# writer.net
KiCad netlist of a schematic drawn in EAGLE
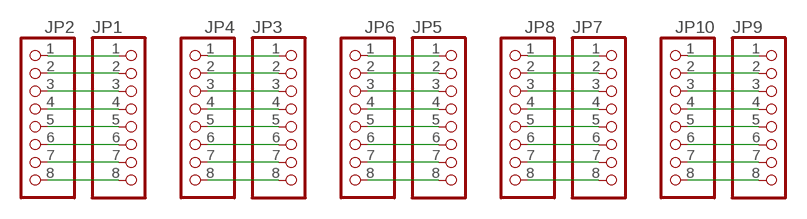
[diagram p0: schematic, sheet 1]

(export (version "E")
  (design (tool "Eeschema 10.0.6"))
  (components
    (comp (ref "JP1")
      (value "PINHD-1X8")
      (footprint "eagle-import:1X08")
      (libsource (lib "eagle-import") (part "PINHD-1X8"))
    )
    (comp (ref "JP2")
      (value "PINHD-1X8")
      (footprint "eagle-import:1X08")
      (libsource (lib "eagle-import") (part "PINHD-1X8"))
    )
    (comp (ref "JP3")
      (value "PINHD-1X8")
      (footprint "eagle-import:1X08")
      (libsource (lib "eagle-import") (part "PINHD-1X8"))
    )
    (comp (ref "JP4")
      (value "PINHD-1X8")
      (footprint "eagle-import:1X08")
      (libsource (lib "eagle-import") (part "PINHD-1X8"))
    )
    (comp (ref "JP5")
      (value "PINHD-1X8")
      (footprint "eagle-import:1X08")
      (libsource (lib "eagle-import") (part "PINHD-1X8"))
    )
    (comp (ref "JP6")
      (value "PINHD-1X8")
      (footprint "eagle-import:1X08")
      (libsource (lib "eagle-import") (part "PINHD-1X8"))
    )
    (comp (ref "JP7")
      (value "PINHD-1X8")
      (footprint "eagle-import:1X08")
      (libsource (lib "eagle-import") (part "PINHD-1X8"))
    )
    (comp (ref "JP8")
      (value "PINHD-1X8")
      (footprint "eagle-import:1X08")
      (libsource (lib "eagle-import") (part "PINHD-1X8"))
    )
    (comp (ref "JP9")
      (value "PINHD-1X8")
      (footprint "eagle-import:1X08")
      (libsource (lib "eagle-import") (part "PINHD-1X8"))
    )
    (comp (ref "JP10")
      (value "PINHD-1X8")
      (footprint "eagle-import:1X08")
      (libsource (lib "eagle-import") (part "PINHD-1X8"))
    )
  )
  (nets
    (net (code "1") (name "Net-(JP1-Pad1)") (class "Default")
      (node (ref "JP1") (pin "1") (pinfunction "1_1") (pintype "passive"))
      (node (ref "JP2") (pin "1") (pinfunction "1_1") (pintype "passive"))
    )
    (net (code "2") (name "Net-(JP1-Pad2)") (class "Default")
      (node (ref "JP1") (pin "2") (pinfunction "2_2") (pintype "passive"))
      (node (ref "JP2") (pin "2") (pinfunction "2_2") (pintype "passive"))
    )
    (net (code "3") (name "Net-(JP1-Pad3)") (class "Default")
      (node (ref "JP1") (pin "3") (pinfunction "3_3") (pintype "passive"))
      (node (ref "JP2") (pin "3") (pinfunction "3_3") (pintype "passive"))
    )
    (net (code "4") (name "Net-(JP1-Pad4)") (class "Default")
      (node (ref "JP1") (pin "4") (pinfunction "4_4") (pintype "passive"))
      (node (ref "JP2") (pin "4") (pinfunction "4_4") (pintype "passive"))
    )
    (net (code "5") (name "Net-(JP1-Pad5)") (class "Default")
      (node (ref "JP1") (pin "5") (pinfunction "5_5") (pintype "passive"))
      (node (ref "JP2") (pin "5") (pinfunction "5_5") (pintype "passive"))
    )
    (net (code "6") (name "Net-(JP1-Pad6)") (class "Default")
      (node (ref "JP1") (pin "6") (pinfunction "6_6") (pintype "passive"))
      (node (ref "JP2") (pin "6") (pinfunction "6_6") (pintype "passive"))
    )
    (net (code "7") (name "Net-(JP1-Pad7)") (class "Default")
      (node (ref "JP1") (pin "7") (pinfunction "7_7") (pintype "passive"))
      (node (ref "JP2") (pin "7") (pinfunction "7_7") (pintype "passive"))
    )
    (net (code "8") (name "Net-(JP1-Pad8)") (class "Default")
      (node (ref "JP1") (pin "8") (pinfunction "8_8") (pintype "passive"))
      (node (ref "JP2") (pin "8") (pinfunction "8_8") (pintype "passive"))
    )
    (net (code "9") (name "Net-(JP3-Pad1)") (class "Default")
      (node (ref "JP3") (pin "1") (pinfunction "1_1") (pintype "passive"))
      (node (ref "JP4") (pin "1") (pinfunction "1_1") (pintype "passive"))
    )
    (net (code "10") (name "Net-(JP3-Pad2)") (class "Default")
      (node (ref "JP3") (pin "2") (pinfunction "2_2") (pintype "passive"))
      (node (ref "JP4") (pin "2") (pinfunction "2_2") (pintype "passive"))
    )
    (net (code "11") (name "Net-(JP3-Pad3)") (class "Default")
      (node (ref "JP3") (pin "3") (pinfunction "3_3") (pintype "passive"))
      (node (ref "JP4") (pin "3") (pinfunction "3_3") (pintype "passive"))
    )
    (net (code "12") (name "Net-(JP3-Pad4)") (class "Default")
      (node (ref "JP3") (pin "4") (pinfunction "4_4") (pintype "passive"))
      (node (ref "JP4") (pin "4") (pinfunction "4_4") (pintype "passive"))
    )
    (net (code "13") (name "Net-(JP3-Pad5)") (class "Default")
      (node (ref "JP3") (pin "5") (pinfunction "5_5") (pintype "passive"))
      (node (ref "JP4") (pin "5") (pinfunction "5_5") (pintype "passive"))
    )
    (net (code "14") (name "Net-(JP3-Pad6)") (class "Default")
      (node (ref "JP3") (pin "6") (pinfunction "6_6") (pintype "passive"))
      (node (ref "JP4") (pin "6") (pinfunction "6_6") (pintype "passive"))
    )
    (net (code "15") (name "Net-(JP3-Pad7)") (class "Default")
      (node (ref "JP3") (pin "7") (pinfunction "7_7") (pintype "passive"))
      (node (ref "JP4") (pin "7") (pinfunction "7_7") (pintype "passive"))
    )
    (net (code "16") (name "Net-(JP3-Pad8)") (class "Default")
      (node (ref "JP3") (pin "8") (pinfunction "8_8") (pintype "passive"))
      (node (ref "JP4") (pin "8") (pinfunction "8_8") (pintype "passive"))
    )
    (net (code "17") (name "Net-(JP5-Pad1)") (class "Default")
      (node (ref "JP5") (pin "1") (pinfunction "1_1") (pintype "passive"))
      (node (ref "JP6") (pin "1") (pinfunction "1_1") (pintype "passive"))
    )
    (net (code "18") (name "Net-(JP5-Pad2)") (class "Default")
      (node (ref "JP5") (pin "2") (pinfunction "2_2") (pintype "passive"))
      (node (ref "JP6") (pin "2") (pinfunction "2_2") (pintype "passive"))
    )
    (net (code "19") (name "Net-(JP5-Pad3)") (class "Default")
      (node (ref "JP5") (pin "3") (pinfunction "3_3") (pintype "passive"))
      (node (ref "JP6") (pin "3") (pinfunction "3_3") (pintype "passive"))
    )
    (net (code "20") (name "Net-(JP5-Pad4)") (class "Default")
      (node (ref "JP5") (pin "4") (pinfunction "4_4") (pintype "passive"))
      (node (ref "JP6") (pin "4") (pinfunction "4_4") (pintype "passive"))
    )
    (net (code "21") (name "Net-(JP5-Pad5)") (class "Default")
      (node (ref "JP5") (pin "5") (pinfunction "5_5") (pintype "passive"))
      (node (ref "JP6") (pin "5") (pinfunction "5_5") (pintype "passive"))
    )
    (net (code "22") (name "Net-(JP5-Pad6)") (class "Default")
      (node (ref "JP5") (pin "6") (pinfunction "6_6") (pintype "passive"))
      (node (ref "JP6") (pin "6") (pinfunction "6_6") (pintype "passive"))
    )
    (net (code "23") (name "Net-(JP5-Pad7)") (class "Default")
      (node (ref "JP5") (pin "7") (pinfunction "7_7") (pintype "passive"))
      (node (ref "JP6") (pin "7") (pinfunction "7_7") (pintype "passive"))
    )
    (net (code "24") (name "Net-(JP5-Pad8)") (class "Default")
      (node (ref "JP5") (pin "8") (pinfunction "8_8") (pintype "passive"))
      (node (ref "JP6") (pin "8") (pinfunction "8_8") (pintype "passive"))
    )
    (net (code "25") (name "Net-(JP7-Pad1)") (class "Default")
      (node (ref "JP7") (pin "1") (pinfunction "1_1") (pintype "passive"))
      (node (ref "JP8") (pin "1") (pinfunction "1_1") (pintype "passive"))
    )
    (net (code "26") (name "Net-(JP7-Pad2)") (class "Default")
      (node (ref "JP7") (pin "2") (pinfunction "2_2") (pintype "passive"))
      (node (ref "JP8") (pin "2") (pinfunction "2_2") (pintype "passive"))
    )
    (net (code "27") (name "Net-(JP7-Pad3)") (class "Default")
      (node (ref "JP7") (pin "3") (pinfunction "3_3") (pintype "passive"))
      (node (ref "JP8") (pin "3") (pinfunction "3_3") (pintype "passive"))
    )
    (net (code "28") (name "Net-(JP7-Pad4)") (class "Default")
      (node (ref "JP7") (pin "4") (pinfunction "4_4") (pintype "passive"))
      (node (ref "JP8") (pin "4") (pinfunction "4_4") (pintype "passive"))
    )
    (net (code "29") (name "Net-(JP7-Pad5)") (class "Default")
      (node (ref "JP7") (pin "5") (pinfunction "5_5") (pintype "passive"))
      (node (ref "JP8") (pin "5") (pinfunction "5_5") (pintype "passive"))
    )
    (net (code "30") (name "Net-(JP7-Pad6)") (class "Default")
      (node (ref "JP7") (pin "6") (pinfunction "6_6") (pintype "passive"))
      (node (ref "JP8") (pin "6") (pinfunction "6_6") (pintype "passive"))
    )
    (net (code "31") (name "Net-(JP7-Pad7)") (class "Default")
      (node (ref "JP7") (pin "7") (pinfunction "7_7") (pintype "passive"))
      (node (ref "JP8") (pin "7") (pinfunction "7_7") (pintype "passive"))
    )
    (net (code "32") (name "Net-(JP7-Pad8)") (class "Default")
      (node (ref "JP7") (pin "8") (pinfunction "8_8") (pintype "passive"))
      (node (ref "JP8") (pin "8") (pinfunction "8_8") (pintype "passive"))
    )
    (net (code "33") (name "Net-(JP10-Pad1)") (class "Default")
      (node (ref "JP10") (pin "1") (pinfunction "1_1") (pintype "passive"))
      (node (ref "JP9") (pin "1") (pinfunction "1_1") (pintype "passive"))
    )
    (net (code "34") (name "Net-(JP10-Pad2)") (class "Default")
      (node (ref "JP10") (pin "2") (pinfunction "2_2") (pintype "passive"))
      (node (ref "JP9") (pin "2") (pinfunction "2_2") (pintype "passive"))
    )
    (net (code "35") (name "Net-(JP10-Pad3)") (class "Default")
      (node (ref "JP10") (pin "3") (pinfunction "3_3") (pintype "passive"))
      (node (ref "JP9") (pin "3") (pinfunction "3_3") (pintype "passive"))
    )
    (net (code "36") (name "Net-(JP10-Pad4)") (class "Default")
      (node (ref "JP10") (pin "4") (pinfunction "4_4") (pintype "passive"))
      (node (ref "JP9") (pin "4") (pinfunction "4_4") (pintype "passive"))
    )
    (net (code "37") (name "Net-(JP10-Pad5)") (class "Default")
      (node (ref "JP10") (pin "5") (pinfunction "5_5") (pintype "passive"))
      (node (ref "JP9") (pin "5") (pinfunction "5_5") (pintype "passive"))
    )
    (net (code "38") (name "Net-(JP10-Pad6)") (class "Default")
      (node (ref "JP10") (pin "6") (pinfunction "6_6") (pintype "passive"))
      (node (ref "JP9") (pin "6") (pinfunction "6_6") (pintype "passive"))
    )
    (net (code "39") (name "Net-(JP10-Pad7)") (class "Default")
      (node (ref "JP10") (pin "7") (pinfunction "7_7") (pintype "passive"))
      (node (ref "JP9") (pin "7") (pinfunction "7_7") (pintype "passive"))
    )
    (net (code "40") (name "Net-(JP10-Pad8)") (class "Default")
      (node (ref "JP10") (pin "8") (pinfunction "8_8") (pintype "passive"))
      (node (ref "JP9") (pin "8") (pinfunction "8_8") (pintype "passive"))
    )
  )
)
